# GPIO_Ex.net
KiCad netlist of a schematic drawn in Altium Designer
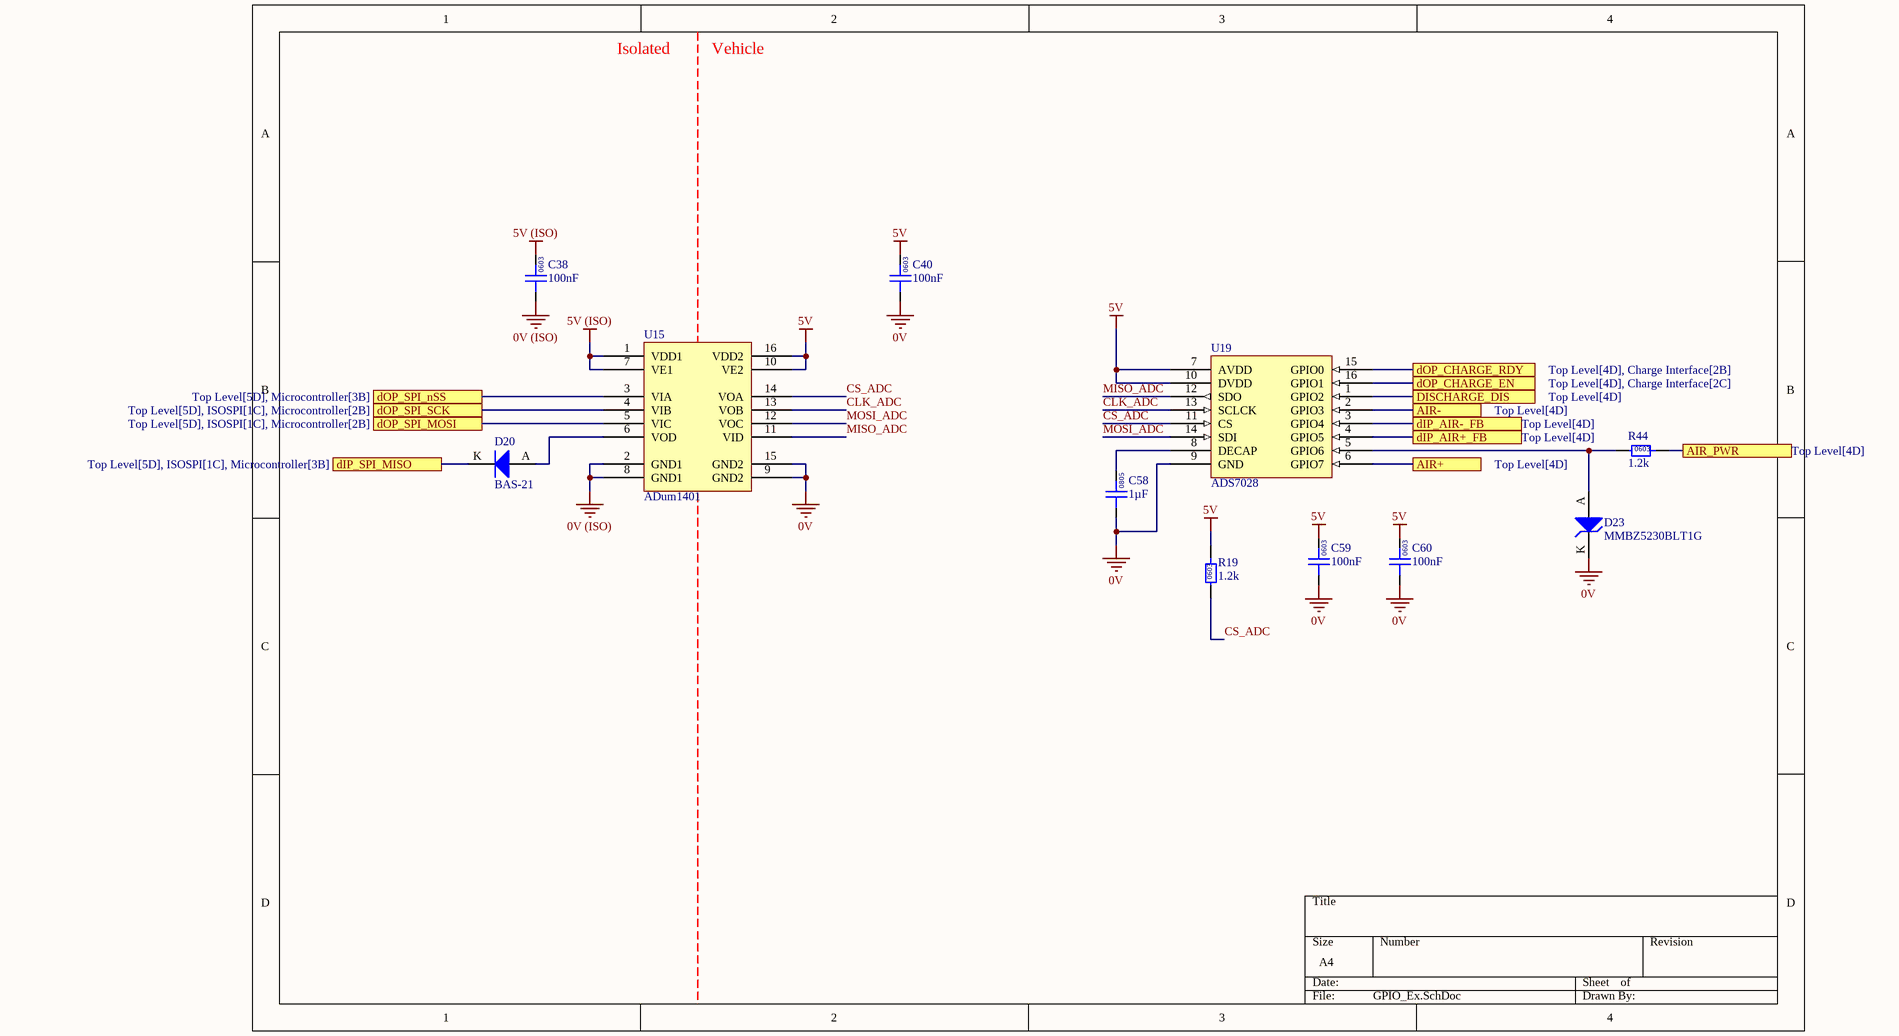
[diagram p0: GPIO_Ex.SchDoc]

(export (version "E")
  (design (tool "Eeschema 10.0.6"))
  (components
    (comp (ref "C38")
      (value "100nF")
      (footprint "0603")
      (fields
        (field (name "PART NUMBER") "GCM188L81H104KA57D")
        (field (name "MANUFACTURER") "muRata")
        (field (name "TOLERANCE") "±10%")
      )
      (libsource (lib "ts_standard_library") (part "Capacitor 0603"))
    )
    (comp (ref "C40")
      (value "100nF")
      (footprint "0603")
      (fields
        (field (name "PART NUMBER") "GCM188L81H104KA57D")
        (field (name "MANUFACTURER") "muRata")
        (field (name "TOLERANCE") "±10%")
      )
      (libsource (lib "ts_standard_library") (part "Capacitor 0603"))
    )
    (comp (ref "C58")
      (value "1µF")
      (footprint "0805")
      (fields
        (field (name "PART NUMBER") "GCM21BR71H105KA03L")
        (field (name "MANUFACTURER") "muRata")
        (field (name "TOLERANCE") "±10%")
      )
      (libsource (lib "ts_standard_library") (part "Capacitor 0805"))
    )
    (comp (ref "C59")
      (value "100nF")
      (footprint "0603")
      (fields
        (field (name "PART NUMBER") "GCM188L81H104KA57D")
        (field (name "MANUFACTURER") "muRata")
        (field (name "TOLERANCE") "±10%")
      )
      (libsource (lib "ts_standard_library") (part "Capacitor 0603"))
    )
    (comp (ref "C60")
      (value "100nF")
      (footprint "0603")
      (fields
        (field (name "PART NUMBER") "GCM188L81H104KA57D")
        (field (name "MANUFACTURER") "muRata")
        (field (name "TOLERANCE") "±10%")
      )
      (libsource (lib "ts_standard_library") (part "Capacitor 0603"))
    )
    (comp (ref "D20")
      (value "BAS-21")
      (footprint "NEXPERIA_SOT23")
      (fields (field (name "MANUFACTURER") "Nexperia USA Inc."))
      (libsource (lib "ts_standard_library") (part "Diode"))
    )
    (comp (ref "D23")
      (value "MMBZ5230BLT1G")
      (footprint "NEXPERIA_SOT23")
      (fields
        (field (name "MANUFACTURER") "onsemi")
        (field (name "DIGIKEY PART NUMBER") "MMBZ5230BLT1GOSTR-ND")
      )
      (libsource (lib "ts_standard_library") (part "Zener Diode"))
    )
    (comp (ref "R19")
      (value "1.2k")
      (footprint "0603")
      (fields
        (field (name "PART NUMBER") "RC0603JR-071K2L")
        (field (name "MANUFACTURER") "YAGEO")
        (field (name "TOLERANCE") "0.01")
      )
      (libsource (lib "ts_standard_library") (part "Resistor 0603"))
    )
    (comp (ref "R44")
      (value "1.2k")
      (footprint "0603")
      (fields
        (field (name "PART NUMBER") "RC0603JR-071K2L")
        (field (name "MANUFACTURER") "YAGEO")
        (field (name "TOLERANCE") "0.01")
      )
      (libsource (lib "ts_standard_library") (part "Resistor 0603"))
    )
    (comp (ref "U15")
      (value "ADum1401")
      (footprint "AD 16-SOIC")
      (fields (field (name "PART NUMBER") "ADuM1401") (field (name "MANUFACTURER") "Analog Devices"))
      (libsource (lib "ts_standard_library") (part "ADum1401"))
    )
    (comp (ref "U19")
      (value "ADS7028")
      (footprint "WFQN-16")
      (description "IC ADC 12BIT SAR 16WQFN")
      (fields (field (name "PART NUMBER") "ADS7028IRTER") (field (name "MANUFACTURER") "Texas Instruments"))
      (libsource (lib "ts_standard_library") (part "ADS7028IRTER"))
    )
  )
  (nets
    (net (code "1") (name "/AIR+") (class "Default")
      (node (ref "U19") (pin "6") (pinfunction "GPIO7_6") (pintype "input"))
    )
    (net (code "2") (name "/AIR-") (class "Default")
      (node (ref "U19") (pin "2") (pinfunction "GPIO3_2") (pintype "input"))
    )
    (net (code "3") (name "/AIR_PWR") (class "Default")
      (node (ref "R44") (pin "2") (pinfunction "2_2") (pintype "passive"))
    )
    (net (code "4") (name "/CLK_ADC") (class "Default")
      (node (ref "U15") (pin "13") (pinfunction "VOB_13") (pintype "passive"))
      (node (ref "U19") (pin "13") (pinfunction "SCLCK_13") (pintype "input"))
    )
    (net (code "5") (name "/CS_ADC") (class "Default")
      (node (ref "R19") (pin "1") (pinfunction "1_1") (pintype "passive"))
      (node (ref "U15") (pin "14") (pinfunction "VOA_14") (pintype "passive"))
      (node (ref "U19") (pin "11") (pinfunction "CS_11") (pintype "input"))
    )
    (net (code "6") (name "/DISCHARGE_DIS") (class "Default")
      (node (ref "U19") (pin "1") (pinfunction "GPIO2_1") (pintype "input"))
    )
    (net (code "7") (name "/MISO_ADC") (class "Default")
      (node (ref "U15") (pin "11") (pinfunction "VID_11") (pintype "passive"))
      (node (ref "U19") (pin "12") (pinfunction "SDO_12") (pintype "output"))
    )
    (net (code "8") (name "/MOSI_ADC") (class "Default")
      (node (ref "U15") (pin "12") (pinfunction "VOC_12") (pintype "passive"))
      (node (ref "U19") (pin "14") (pinfunction "SDI_14") (pintype "input"))
    )
    (net (code "9") (name "/dIP_AIR+_FB") (class "Default")
      (node (ref "U19") (pin "4") (pinfunction "GPIO5_4") (pintype "input"))
    )
    (net (code "10") (name "/dIP_AIR-_FB") (class "Default")
      (node (ref "U19") (pin "3") (pinfunction "GPIO4_3") (pintype "input"))
    )
    (net (code "11") (name "/dIP_SPI_MISO") (class "Default")
      (node (ref "D20") (pin "K") (pinfunction "K_K") (pintype "passive"))
    )
    (net (code "12") (name "/dOP_CHARGE_EN") (class "Default")
      (node (ref "U19") (pin "16") (pinfunction "GPIO1_16") (pintype "input"))
    )
    (net (code "13") (name "/dOP_CHARGE_RDY") (class "Default")
      (node (ref "U19") (pin "15") (pinfunction "GPIO0_15") (pintype "input"))
    )
    (net (code "14") (name "/dOP_SPI_MOSI") (class "Default")
      (node (ref "U15") (pin "5") (pinfunction "VIC_5") (pintype "passive"))
    )
    (net (code "15") (name "/dOP_SPI_SCK") (class "Default")
      (node (ref "U15") (pin "4") (pinfunction "VIB_4") (pintype "passive"))
    )
    (net (code "16") (name "/dOP_SPI_nSS") (class "Default")
      (node (ref "U15") (pin "3") (pinfunction "VIA_3") (pintype "passive"))
    )
    (net (code "17") (name "0V") (class "Default")
      (node (ref "C40") (pin "1") (pinfunction "1_1") (pintype "passive"))
      (node (ref "C58") (pin "1") (pinfunction "1_1") (pintype "passive"))
      (node (ref "C59") (pin "1") (pinfunction "1_1") (pintype "passive"))
      (node (ref "C60") (pin "1") (pinfunction "1_1") (pintype "passive"))
      (node (ref "D23") (pin "K") (pinfunction "K_K") (pintype "passive"))
      (node (ref "U15") (pin "15") (pinfunction "GND2_15") (pintype "passive"))
      (node (ref "U15") (pin "9") (pinfunction "GND2_9") (pintype "passive"))
      (node (ref "U19") (pin "9") (pinfunction "GND_9") (pintype "power_in"))
    )
    (net (code "18") (name "0V (ISO)") (class "Default")
      (node (ref "C38") (pin "1") (pinfunction "1_1") (pintype "passive"))
      (node (ref "U15") (pin "2") (pinfunction "GND1_2") (pintype "passive"))
      (node (ref "U15") (pin "8") (pinfunction "GND1_8") (pintype "passive"))
    )
    (net (code "19") (name "5V") (class "Default")
      (node (ref "C40") (pin "2") (pinfunction "2_2") (pintype "passive"))
      (node (ref "C59") (pin "2") (pinfunction "2_2") (pintype "passive"))
      (node (ref "C60") (pin "2") (pinfunction "2_2") (pintype "passive"))
      (node (ref "R19") (pin "2") (pinfunction "2_2") (pintype "passive"))
      (node (ref "U15") (pin "10") (pinfunction "VE2_10") (pintype "passive"))
      (node (ref "U15") (pin "16") (pinfunction "VDD2_16") (pintype "passive"))
      (node (ref "U19") (pin "10") (pinfunction "DVDD_10") (pintype "power_in"))
      (node (ref "U19") (pin "7") (pinfunction "AVDD_7") (pintype "power_in"))
    )
    (net (code "20") (name "5V (ISO)") (class "Default")
      (node (ref "C38") (pin "2") (pinfunction "2_2") (pintype "passive"))
      (node (ref "U15") (pin "1") (pinfunction "VDD1_1") (pintype "passive"))
      (node (ref "U15") (pin "7") (pinfunction "VE1_7") (pintype "passive"))
    )
    (net (code "21") (name "Net-(U15-VOD)") (class "Default")
      (node (ref "D20") (pin "A") (pinfunction "A_A") (pintype "passive"))
      (node (ref "U15") (pin "6") (pinfunction "VOD_6") (pintype "passive"))
    )
    (net (code "22") (name "Net-(U19-DECAP)") (class "Default")
      (node (ref "C58") (pin "2") (pinfunction "2_2") (pintype "passive"))
      (node (ref "U19") (pin "8") (pinfunction "DECAP_8") (pintype "power_in"))
    )
    (net (code "23") (name "Net-(U19-GPIO6)") (class "Default")
      (node (ref "D23") (pin "A") (pinfunction "A_A") (pintype "passive"))
      (node (ref "R44") (pin "1") (pinfunction "1_1") (pintype "passive"))
      (node (ref "U19") (pin "5") (pinfunction "GPIO6_5") (pintype "input"))
    )
  )
)
